# controller.net
KiCad netlist of a schematic drawn in Altium Designer
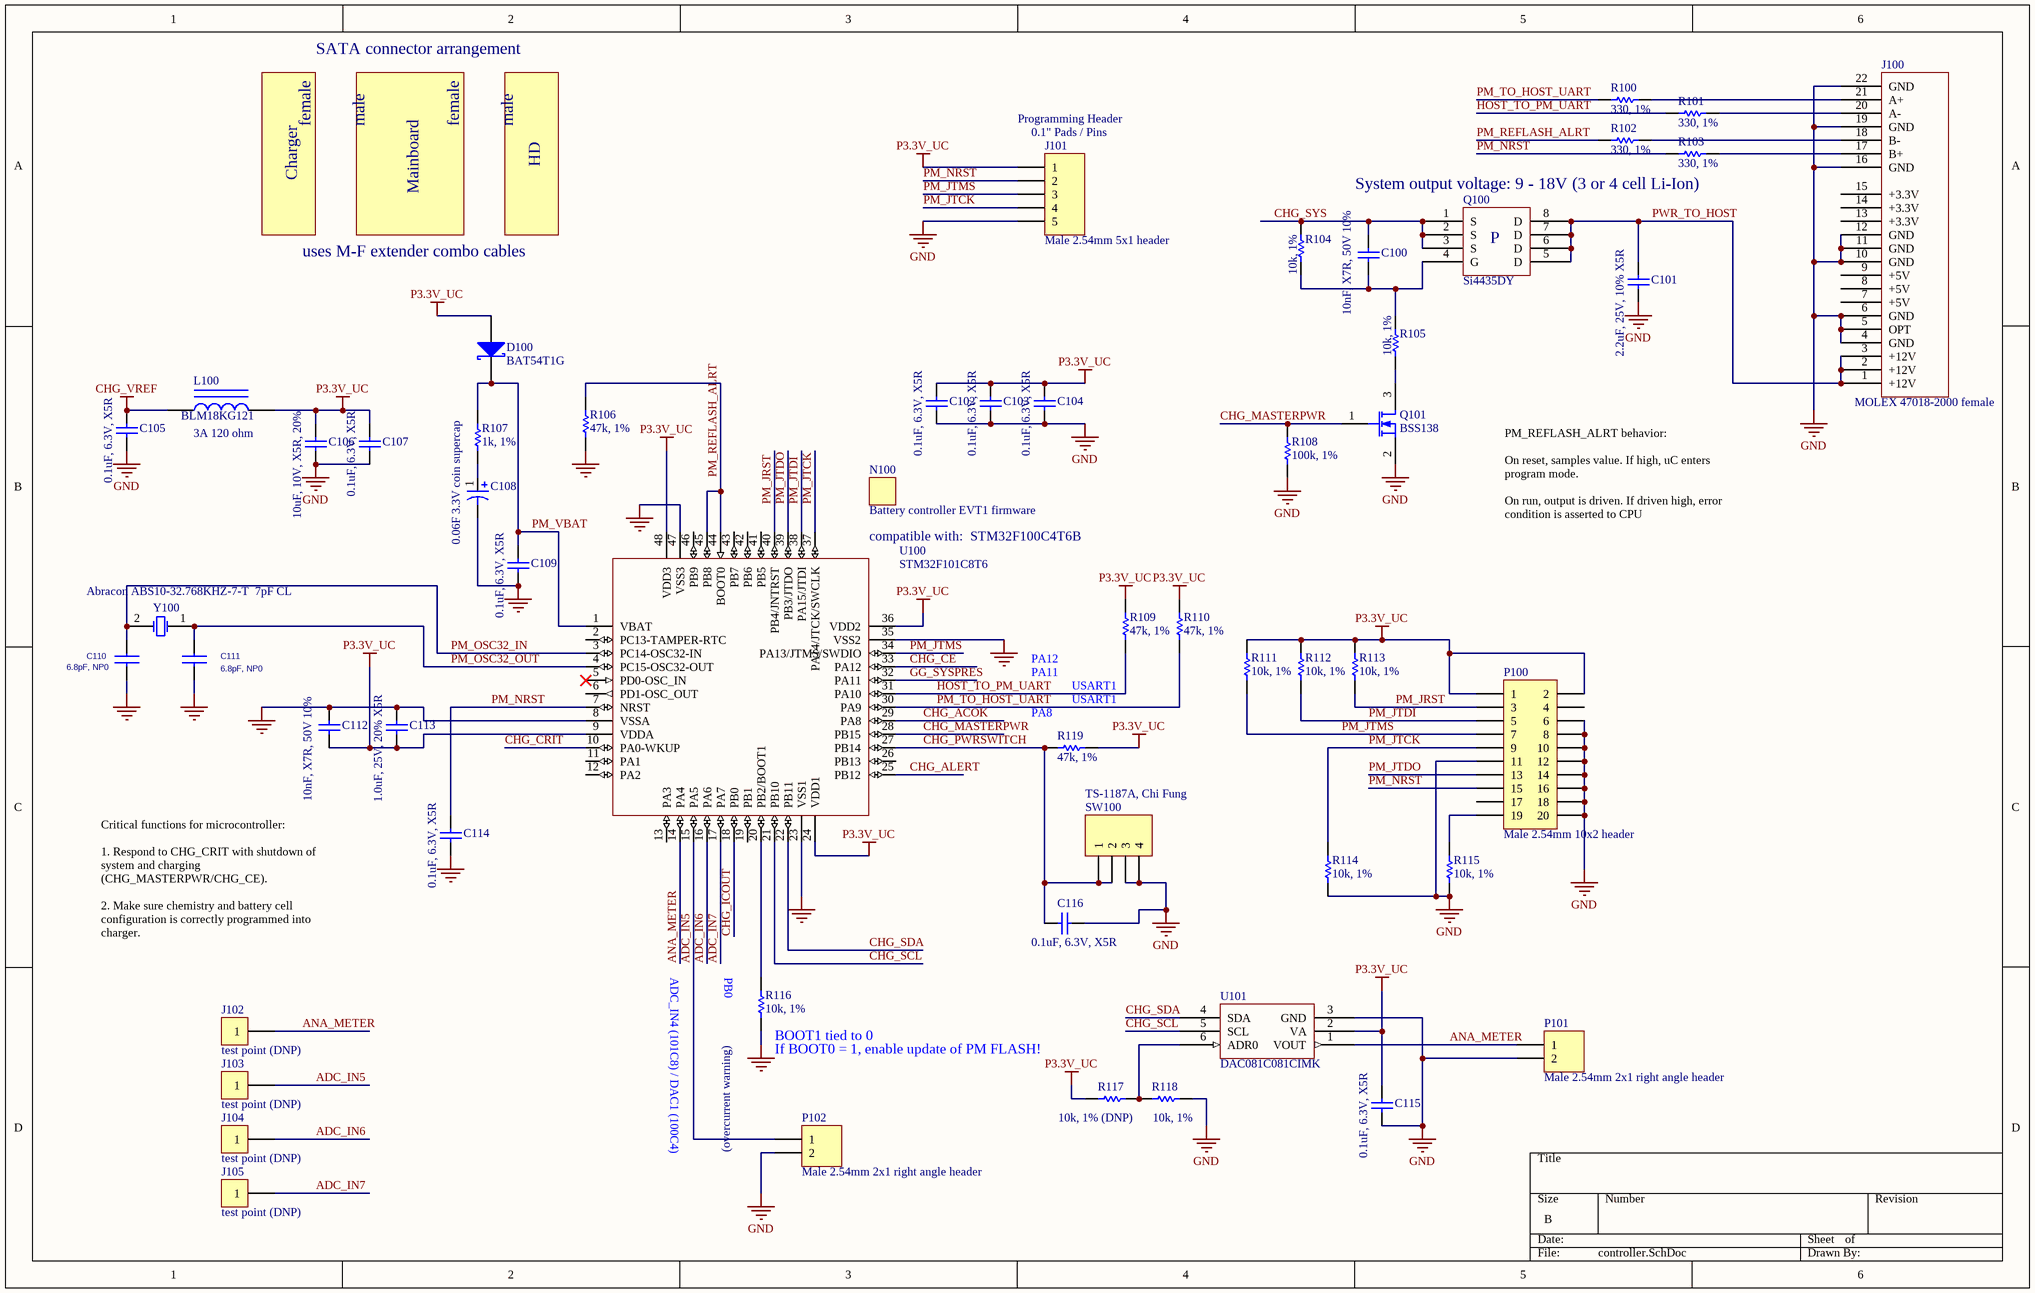
[diagram p0: controller.SchDoc]

(export (version "E")
  (design (tool "Eeschema 10.0.6"))
  (components
    (comp (ref "C100")
      (value "10nF, X7R, 50V 10%")
      (footprint "CAPC1005N")
      (description "Capacitor (Semiconductor SIM Model)")
      (fields (field (name "PUBLISHER") "Altium Limited"))
      (libsource (lib "Miscellaneous Devices") (part "Cap Semi"))
    )
    (comp (ref "C101")
      (value "2.2uF, 25V, 10% X5R")
      (footprint "CAPC1608N")
      (description "Capacitor (Semiconductor SIM Model)")
      (fields (field (name "PUBLISHER") "Altium Limited"))
      (libsource (lib "Miscellaneous Devices") (part "Cap Semi"))
    )
    (comp (ref "C102")
      (value "0.1uF, 6.3V, X5R")
      (footprint "CAPC0603N_B")
      (description "Capacitor (Semiconductor SIM Model)")
      (fields (field (name "PUBLISHER") "Altium Limited"))
      (libsource (lib "Miscellaneous Devices") (part "Cap Semi"))
    )
    (comp (ref "C103")
      (value "0.1uF, 6.3V, X5R")
      (footprint "CAPC0603N_B")
      (description "Capacitor (Semiconductor SIM Model)")
      (fields (field (name "PUBLISHER") "Altium Limited"))
      (libsource (lib "Miscellaneous Devices") (part "Cap Semi"))
    )
    (comp (ref "C104")
      (value "0.1uF, 6.3V, X5R")
      (footprint "CAPC0603N_B")
      (description "Capacitor (Semiconductor SIM Model)")
      (fields (field (name "PUBLISHER") "Altium Limited"))
      (libsource (lib "Miscellaneous Devices") (part "Cap Semi"))
    )
    (comp (ref "C105")
      (value "0.1uF, 6.3V, X5R")
      (footprint "CAPC0603N_B")
      (description "Capacitor (Semiconductor SIM Model)")
      (fields (field (name "PUBLISHER") "Altium Limited"))
      (libsource (lib "Miscellaneous Devices") (part "Cap Semi"))
    )
    (comp (ref "C106")
      (value "10uF, 10V, X5R, 20%")
      (footprint "CAPC1608N")
      (description "Capacitor (Semiconductor SIM Model)")
      (fields (field (name "PUBLISHER") "Altium Limited"))
      (libsource (lib "Miscellaneous Devices") (part "Cap Semi"))
    )
    (comp (ref "C107")
      (value "0.1uF, 6.3V, X5R")
      (footprint "CAPC0603N_B")
      (description "Capacitor (Semiconductor SIM Model)")
      (fields (field (name "PUBLISHER") "Altium Limited"))
      (libsource (lib "Miscellaneous Devices") (part "Cap Semi"))
    )
    (comp (ref "C108")
      (value "0.06F 3.3V coin supercap")
      (footprint "TAIYO_YUDEN_PAS414HR-VA5R")
      (description "Taiyo Yuden PAS414HR-VA5R")
      (fields (field (name "PUBLISHER") "Altium Limited"))
      (libsource (lib "Miscellaneous Devices") (part "Cap Pol3"))
    )
    (comp (ref "C109")
      (value "0.1uF, 6.3V, X5R")
      (footprint "CAPC0603N_B")
      (description "Capacitor (Semiconductor SIM Model)")
      (fields (field (name "PUBLISHER") "Altium Limited"))
      (libsource (lib "Miscellaneous Devices") (part "Cap Semi"))
    )
    (comp (ref "C110") (value "6.8pF, NP0") (libsource (lib "*") (part "CAP NP")))
    (comp (ref "C111") (value "6.8pF, NP0") (libsource (lib "*") (part "CAP NP")))
    (comp (ref "C112")
      (value "10nF, X7R, 50V 10%")
      (footprint "CAPC1005N")
      (description "Capacitor (Semiconductor SIM Model)")
      (fields (field (name "PUBLISHER") "Altium Limited"))
      (libsource (lib "Miscellaneous Devices") (part "Cap Semi"))
    )
    (comp (ref "C113")
      (value "1.0uF, 25V, 20% X5R")
      (footprint "CAPC1608N")
      (description "Capacitor (Semiconductor SIM Model)")
      (fields (field (name "PUBLISHER") "Altium Limited"))
      (libsource (lib "Miscellaneous Devices") (part "Cap Semi"))
    )
    (comp (ref "C114")
      (value "0.1uF, 6.3V, X5R")
      (footprint "CAPC0603N_B")
      (description "Capacitor (Semiconductor SIM Model)")
      (fields (field (name "PUBLISHER") "Altium Limited"))
      (libsource (lib "Miscellaneous Devices") (part "Cap Semi"))
    )
    (comp (ref "C115")
      (value "0.1uF, 6.3V, X5R")
      (footprint "CAPC0603N_B")
      (description "Capacitor (Semiconductor SIM Model)")
      (fields (field (name "PUBLISHER") "Altium Limited"))
      (libsource (lib "Miscellaneous Devices") (part "Cap Semi"))
    )
    (comp (ref "C116")
      (value "0.1uF, 6.3V, X5R")
      (footprint "CAPC0603N_B")
      (description "Capacitor (Semiconductor SIM Model)")
      (fields (field (name "PUBLISHER") "Altium Limited"))
      (libsource (lib "Miscellaneous Devices") (part "Cap Semi"))
    )
    (comp (ref "D100")
      (value "BAT54T1G")
      (footprint "SOD123")
      (description "Schottky Diode")
      (fields (field (name "PUBLISHER") "Altium Limited"))
      (libsource (lib "Miscellaneous Devices") (part "D Schottky"))
    )
    (comp (ref "J100")
      (value "MOLEX 47018-2000 female")
      (footprint "SATA_MOLEX_47018_2000")
      (description "SATA+Power connector")
      (libsource (lib "commonsch") (part "SATA_22P_HEADER"))
    )
    (comp (ref "J101")
      (value "Male 2.54mm 5x1 header")
      (footprint "HDR1X5")
      (description "Header, 5-Pin")
      (fields (field (name "PUBLISHER") "Altium Limited"))
      (libsource (lib "Miscellaneous Connectors") (part "Header 5"))
    )
    (comp (ref "J102")
      (value "test point (DNP)")
      (footprint "TP_SMT_38mil")
      (description "Connector")
      (libsource (lib "*") (part "CON1"))
    )
    (comp (ref "J103")
      (value "test point (DNP)")
      (footprint "TP_SMT_38mil")
      (description "Connector")
      (libsource (lib "*") (part "CON1"))
    )
    (comp (ref "J104")
      (value "test point (DNP)")
      (footprint "TP_SMT_38mil")
      (description "Connector")
      (libsource (lib "*") (part "CON1"))
    )
    (comp (ref "J105")
      (value "test point (DNP)")
      (footprint "TP_SMT_38mil")
      (description "Connector")
      (libsource (lib "*") (part "CON1"))
    )
    (comp (ref "L100")
      (value "BLM18KG121")
      (footprint "INDC1608AN")
      (description "Magnetic-Core Inductor")
      (fields (field (name "ALTIUM_VALUE") "3A 120 ohm") (field (name "PUBLISHER") "Altium Limited"))
      (libsource (lib "Miscellaneous Devices") (part "Inductor Iron"))
    )
    (comp (ref "N100")
      (value "Battery controller EVT1 firmware")
      (description "Placeholder for non-electrical BOM items")
      (libsource (lib "commonsch") (part "NOTE"))
    )
    (comp (ref "P100")
      (value "Male 2.54mm 10x2 header")
      (footprint "HDR2X10")
      (description "Header, 10-Pin, Dual row")
      (fields (field (name "PUBLISHER") "Altium Limited"))
      (libsource (lib "Miscellaneous Connectors") (part "Header 10X2"))
    )
    (comp (ref "P101")
      (value "Male 2.54mm 2x1 right angle header")
      (footprint "HDR1X2H")
      (description "Header, 2-Pin, Right Angle")
      (fields (field (name "PUBLISHER") "Altium Limited"))
      (libsource (lib "Miscellaneous Connectors") (part "Header 2H"))
    )
    (comp (ref "P102")
      (value "Male 2.54mm 2x1 right angle header")
      (footprint "HDR1X2H")
      (description "Header, 2-Pin, Right Angle")
      (fields (field (name "PUBLISHER") "Altium Limited"))
      (libsource (lib "Miscellaneous Connectors") (part "Header 2H"))
    )
    (comp (ref "Q100")
      (value "Si4435DY")
      (footprint "SOIC127P600-8AN")
      (description "Singre P-channel FET, 8A, 30V")
      (libsource (lib "commonsch") (part "Si4435DY"))
    )
    (comp (ref "Q101")
      (value "BSS138")
      (footprint "SOT23-3N")
      (description "N-Channel MOSFET")
      (fields (field (name "PUBLISHER") "Altium Limited"))
      (libsource (lib "Miscellaneous Devices") (part "MOSFET-N"))
    )
    (comp (ref "R100")
      (value "330, 1%")
      (footprint "RESC1005N")
      (description "Resistor")
      (fields (field (name "PUBLISHER") "Altium Limited"))
      (libsource (lib "Miscellaneous Devices") (part "Res1"))
    )
    (comp (ref "R101")
      (value "330, 1%")
      (footprint "RESC1005N")
      (description "Resistor")
      (fields (field (name "PUBLISHER") "Altium Limited"))
      (libsource (lib "Miscellaneous Devices") (part "Res1"))
    )
    (comp (ref "R102")
      (value "330, 1%")
      (footprint "RESC1005N")
      (description "Resistor")
      (fields (field (name "PUBLISHER") "Altium Limited"))
      (libsource (lib "Miscellaneous Devices") (part "Res1"))
    )
    (comp (ref "R103")
      (value "330, 1%")
      (footprint "RESC1005N")
      (description "Resistor")
      (fields (field (name "PUBLISHER") "Altium Limited"))
      (libsource (lib "Miscellaneous Devices") (part "Res1"))
    )
    (comp (ref "R104")
      (value "10k, 1%")
      (footprint "RESC1005N")
      (description "Resistor")
      (fields (field (name "PUBLISHER") "Altium Limited"))
      (libsource (lib "Miscellaneous Devices") (part "Res1"))
    )
    (comp (ref "R105")
      (value "10k, 1%")
      (footprint "RESC1005N")
      (description "Resistor")
      (fields (field (name "PUBLISHER") "Altium Limited"))
      (libsource (lib "Miscellaneous Devices") (part "Res1"))
    )
    (comp (ref "R106")
      (value "47k, 1%")
      (footprint "RESC1005N")
      (description "Resistor")
      (fields (field (name "PUBLISHER") "Altium Limited"))
      (libsource (lib "Miscellaneous Devices") (part "Res1"))
    )
    (comp (ref "R107")
      (value "1k, 1%")
      (footprint "RESC1005N")
      (description "Resistor")
      (fields (field (name "PUBLISHER") "Altium Limited"))
      (libsource (lib "Miscellaneous Devices") (part "Res1"))
    )
    (comp (ref "R108")
      (value "100k, 1%")
      (footprint "RESC1005N")
      (description "Resistor")
      (fields (field (name "PUBLISHER") "Altium Limited"))
      (libsource (lib "Miscellaneous Devices") (part "Res1"))
    )
    (comp (ref "R109")
      (value "47k, 1%")
      (footprint "RESC1005N")
      (description "Resistor")
      (fields (field (name "PUBLISHER") "Altium Limited"))
      (libsource (lib "Miscellaneous Devices") (part "Res1"))
    )
    (comp (ref "R110")
      (value "47k, 1%")
      (footprint "RESC1005N")
      (description "Resistor")
      (fields (field (name "PUBLISHER") "Altium Limited"))
      (libsource (lib "Miscellaneous Devices") (part "Res1"))
    )
    (comp (ref "R111")
      (value "10k, 1%")
      (footprint "RESC1005N")
      (description "Resistor")
      (fields (field (name "PUBLISHER") "Altium Limited"))
      (libsource (lib "Miscellaneous Devices") (part "Res1"))
    )
    (comp (ref "R112")
      (value "10k, 1%")
      (footprint "RESC1005N")
      (description "Resistor")
      (fields (field (name "PUBLISHER") "Altium Limited"))
      (libsource (lib "Miscellaneous Devices") (part "Res1"))
    )
    (comp (ref "R113")
      (value "10k, 1%")
      (footprint "RESC1005N")
      (description "Resistor")
      (fields (field (name "PUBLISHER") "Altium Limited"))
      (libsource (lib "Miscellaneous Devices") (part "Res1"))
    )
    (comp (ref "R114")
      (value "10k, 1%")
      (footprint "RESC1005N")
      (description "Resistor")
      (fields (field (name "PUBLISHER") "Altium Limited"))
      (libsource (lib "Miscellaneous Devices") (part "Res1"))
    )
    (comp (ref "R115")
      (value "10k, 1%")
      (footprint "RESC1005N")
      (description "Resistor")
      (fields (field (name "PUBLISHER") "Altium Limited"))
      (libsource (lib "Miscellaneous Devices") (part "Res1"))
    )
    (comp (ref "R116")
      (value "10k, 1%")
      (footprint "RESC1005N")
      (description "Resistor")
      (fields (field (name "PUBLISHER") "Altium Limited"))
      (libsource (lib "Miscellaneous Devices") (part "Res1"))
    )
    (comp (ref "R117")
      (value "10k, 1% (DNP)")
      (footprint "RESC1005N")
      (description "Resistor")
      (fields (field (name "PUBLISHER") "Altium Limited"))
      (libsource (lib "Miscellaneous Devices") (part "Res1"))
    )
    (comp (ref "R118")
      (value "10k, 1%")
      (footprint "RESC1005N")
      (description "Resistor")
      (fields (field (name "PUBLISHER") "Altium Limited"))
      (libsource (lib "Miscellaneous Devices") (part "Res1"))
    )
    (comp (ref "R119")
      (value "47k, 1%")
      (footprint "RESC1005N")
      (description "Resistor")
      (fields (field (name "PUBLISHER") "Altium Limited"))
      (libsource (lib "Miscellaneous Devices") (part "Res1"))
    )
    (comp (ref "SW100")
      (value "TS-1187A, Chi Fung")
      (footprint "SWITCH_TS-1187A")
      (description "Chi Fung TS-1187A")
      (fields (field (name "PUBLISHER") "Altium Limited"))
      (libsource (lib "Miscellaneous Connectors") (part "Header 4"))
    )
    (comp (ref "U100")
      (value "STM32F101C8T6")
      (footprint "TSQFP50P900X900-48N")
      (description "32-bit ARM Coretex high performance microcontroller")
      (libsource (lib "*") (part "STM32F103C8T6"))
    )
    (comp (ref "U101")
      (value "DAC081C081CIMK")
      (footprint "SOT26A-6N")
      (description "Single 8-bit DAC for I2C bus")
      (libsource (lib "commonsch") (part "DAC081C81CIMK"))
    )
    (comp (ref "Y100")
      (value "Abracon ABS10-32.768KHZ-7-T  7pF CL")
      (footprint "ABS10-32.768KHZ")
      (description "Crystal Oscillator")
      (fields (field (name "PUBLISHER") "Altium Limited"))
      (libsource (lib "Miscellaneous Devices") (part "XTAL"))
    )
  )
  (nets
    (net (code "1") (name "/ADC_IN5") (class "Default")
      (node (ref "J103") (pin "1") (pinfunction "1_1") (pintype "passive"))
      (node (ref "P102") (pin "1") (pinfunction "1_1") (pintype "passive"))
      (node (ref "U100") (pin "15") (pinfunction "PA5_15") (pintype "bidirectional"))
    )
    (net (code "2") (name "/ADC_IN6") (class "Default")
      (node (ref "J104") (pin "1") (pinfunction "1_1") (pintype "passive"))
      (node (ref "U100") (pin "16") (pinfunction "PA6_16") (pintype "bidirectional"))
    )
    (net (code "3") (name "/ADC_IN7") (class "Default")
      (node (ref "J105") (pin "1") (pinfunction "1_1") (pintype "passive"))
      (node (ref "U100") (pin "17") (pinfunction "PA7_17") (pintype "bidirectional"))
    )
    (net (code "4") (name "/ANA_METER") (class "Default")
      (node (ref "J102") (pin "1") (pinfunction "1_1") (pintype "passive"))
      (node (ref "P101") (pin "1") (pinfunction "1_1") (pintype "passive"))
      (node (ref "U100") (pin "14") (pinfunction "PA4_14") (pintype "bidirectional"))
      (node (ref "U101") (pin "1") (pinfunction "VOUT_1") (pintype "output"))
    )
    (net (code "5") (name "/CHG_ACOK") (class "Default")
      (node (ref "U100") (pin "29") (pinfunction "PA8_29") (pintype "bidirectional"))
    )
    (net (code "6") (name "/CHG_ALERT") (class "Default")
      (node (ref "U100") (pin "25") (pinfunction "PB12_25") (pintype "bidirectional"))
    )
    (net (code "7") (name "/CHG_CE") (class "Default")
      (node (ref "U100") (pin "33") (pinfunction "PA12_33") (pintype "bidirectional"))
    )
    (net (code "8") (name "/CHG_CRIT") (class "Default")
      (node (ref "U100") (pin "10") (pinfunction "PA0-WKUP_10") (pintype "bidirectional"))
    )
    (net (code "9") (name "/CHG_ICOUT") (class "Default")
      (node (ref "U100") (pin "18") (pinfunction "PB0_18") (pintype "bidirectional"))
    )
    (net (code "10") (name "/CHG_MASTERPWR") (class "Default")
      (node (ref "Q101") (pin "1") (pinfunction "G_1") (pintype "passive"))
      (node (ref "R108") (pin "2") (pinfunction "2_2") (pintype "passive"))
      (node (ref "U100") (pin "28") (pinfunction "PB15_28") (pintype "bidirectional"))
    )
    (net (code "11") (name "/CHG_PWRSWITCH") (class "Default")
      (node (ref "C116") (pin "2") (pinfunction "2_2") (pintype "passive"))
      (node (ref "R119") (pin "1") (pinfunction "1_1") (pintype "passive"))
      (node (ref "SW100") (pin "1") (pinfunction "1_1") (pintype "passive"))
      (node (ref "SW100") (pin "2") (pinfunction "2_2") (pintype "passive"))
      (node (ref "U100") (pin "27") (pinfunction "PB14_27") (pintype "bidirectional"))
    )
    (net (code "12") (name "/CHG_SCL") (class "Default")
      (node (ref "U100") (pin "21") (pinfunction "PB10_21") (pintype "bidirectional"))
      (node (ref "U101") (pin "5") (pinfunction "SCL_5") (pintype "open_collector"))
    )
    (net (code "13") (name "/CHG_SDA") (class "Default")
      (node (ref "U100") (pin "22") (pinfunction "PB11_22") (pintype "bidirectional"))
      (node (ref "U101") (pin "4") (pinfunction "SDA_4") (pintype "open_collector"))
    )
    (net (code "14") (name "/CHG_SYS") (class "Default")
      (node (ref "C100") (pin "1") (pinfunction "1_1") (pintype "passive"))
      (node (ref "Q100") (pin "1") (pinfunction "S_1") (pintype "passive"))
      (node (ref "Q100") (pin "2") (pinfunction "S_2") (pintype "passive"))
      (node (ref "Q100") (pin "3") (pinfunction "S_3") (pintype "passive"))
      (node (ref "R104") (pin "2") (pinfunction "2_2") (pintype "passive"))
    )
    (net (code "15") (name "/GG_SYSPRES") (class "Default")
      (node (ref "U100") (pin "32") (pinfunction "PA11_32") (pintype "bidirectional"))
    )
    (net (code "16") (name "/HOST_TO_PM_UART") (class "Default")
      (node (ref "R101") (pin "1") (pinfunction "1_1") (pintype "passive"))
      (node (ref "R109") (pin "1") (pinfunction "1_1") (pintype "passive"))
      (node (ref "U100") (pin "31") (pinfunction "PA10_31") (pintype "bidirectional"))
    )
    (net (code "17") (name "/PM_JRST") (class "Default")
      (node (ref "P100") (pin "3") (pinfunction "3_3") (pintype "passive"))
      (node (ref "R113") (pin "1") (pinfunction "1_1") (pintype "passive"))
      (node (ref "U100") (pin "40") (pinfunction "PB4/JNTRST_40") (pintype "bidirectional"))
    )
    (net (code "18") (name "/PM_JTCK") (class "Default")
      (node (ref "J101") (pin "4") (pinfunction "4_4") (pintype "passive"))
      (node (ref "P100") (pin "9") (pinfunction "9_9") (pintype "passive"))
      (node (ref "R114") (pin "2") (pinfunction "2_2") (pintype "passive"))
      (node (ref "U100") (pin "37") (pinfunction "PA14/JTCK/SWCLK_37") (pintype "bidirectional"))
    )
    (net (code "19") (name "/PM_JTDI") (class "Default")
      (node (ref "P100") (pin "5") (pinfunction "5_5") (pintype "passive"))
      (node (ref "R112") (pin "1") (pinfunction "1_1") (pintype "passive"))
      (node (ref "U100") (pin "38") (pinfunction "PA15/JTDI_38") (pintype "bidirectional"))
    )
    (net (code "20") (name "/PM_JTDO") (class "Default")
      (node (ref "P100") (pin "13") (pinfunction "13_13") (pintype "passive"))
      (node (ref "U100") (pin "39") (pinfunction "PB3/JTDO_39") (pintype "bidirectional"))
    )
    (net (code "21") (name "/PM_JTMS") (class "Default")
      (node (ref "J101") (pin "3") (pinfunction "3_3") (pintype "passive"))
      (node (ref "P100") (pin "7") (pinfunction "7_7") (pintype "passive"))
      (node (ref "R111") (pin "1") (pinfunction "1_1") (pintype "passive"))
      (node (ref "U100") (pin "34") (pinfunction "PA13/JTMS/SWDIO_34") (pintype "bidirectional"))
    )
    (net (code "22") (name "/PM_NRST") (class "Default")
      (node (ref "C114") (pin "1") (pinfunction "1_1") (pintype "passive"))
      (node (ref "J101") (pin "2") (pinfunction "2_2") (pintype "passive"))
      (node (ref "P100") (pin "15") (pinfunction "15_15") (pintype "passive"))
      (node (ref "R103") (pin "1") (pinfunction "1_1") (pintype "passive"))
      (node (ref "U100") (pin "7") (pinfunction "NRST_7") (pintype "bidirectional"))
    )
    (net (code "23") (name "/PM_OSC32_IN") (class "Default")
      (node (ref "C110") (pin "1") (pinfunction "1_1") (pintype "passive"))
      (node (ref "U100") (pin "3") (pinfunction "PC14-OSC32-IN_3") (pintype "bidirectional"))
      (node (ref "Y100") (pin "2") (pinfunction "OSC2_2") (pintype "passive"))
    )
    (net (code "24") (name "/PM_OSC32_OUT") (class "Default")
      (node (ref "C111") (pin "1") (pinfunction "1_1") (pintype "passive"))
      (node (ref "U100") (pin "4") (pinfunction "PC15-OSC32-OUT_4") (pintype "bidirectional"))
      (node (ref "Y100") (pin "1") (pinfunction "OSC1_1") (pintype "passive"))
    )
    (net (code "25") (name "/PM_REFLASH_ALRT") (class "Default")
      (node (ref "R102") (pin "1") (pinfunction "1_1") (pintype "passive"))
      (node (ref "R106") (pin "2") (pinfunction "2_2") (pintype "passive"))
      (node (ref "U100") (pin "44") (pinfunction "BOOT0_44") (pintype "input"))
      (node (ref "U100") (pin "45") (pinfunction "PB8_45") (pintype "bidirectional"))
    )
    (net (code "26") (name "/PM_TO_HOST_UART") (class "Default")
      (node (ref "R100") (pin "1") (pinfunction "1_1") (pintype "passive"))
      (node (ref "R110") (pin "1") (pinfunction "1_1") (pintype "passive"))
      (node (ref "U100") (pin "30") (pinfunction "PA9_30") (pintype "bidirectional"))
    )
    (net (code "27") (name "/PM_VBAT") (class "Default")
      (node (ref "C109") (pin "1") (pinfunction "1_1") (pintype "passive"))
      (node (ref "D100") (pin "2") (pinfunction "K_2") (pintype "passive"))
      (node (ref "R107") (pin "2") (pinfunction "2_2") (pintype "passive"))
      (node (ref "U100") (pin "1") (pinfunction "VBAT_1") (pintype "power_in"))
    )
    (net (code "28") (name "/PWR_TO_HOST") (class "Default")
      (node (ref "C101") (pin "1") (pinfunction "1_1") (pintype "passive"))
      (node (ref "J100") (pin "1") (pinfunction "+12V_1") (pintype "power_in"))
      (node (ref "J100") (pin "2") (pinfunction "+12V_2") (pintype "power_in"))
      (node (ref "J100") (pin "3") (pinfunction "+12V_3") (pintype "power_in"))
      (node (ref "Q100") (pin "5") (pinfunction "D_5") (pintype "passive"))
      (node (ref "Q100") (pin "6") (pinfunction "D_6") (pintype "passive"))
      (node (ref "Q100") (pin "7") (pinfunction "D_7") (pintype "passive"))
      (node (ref "Q100") (pin "8") (pinfunction "D_8") (pintype "passive"))
    )
    (net (code "29") (name "CHG_VREF") (class "Default")
      (node (ref "C105") (pin "1") (pinfunction "1_1") (pintype "passive"))
      (node (ref "L100") (pin "1") (pinfunction "1_1") (pintype "passive"))
    )
    (net (code "30") (name "GND") (class "Default")
      (node (ref "C101") (pin "2") (pinfunction "2_2") (pintype "passive"))
      (node (ref "C102") (pin "2") (pinfunction "2_2") (pintype "passive"))
      (node (ref "C103") (pin "2") (pinfunction "2_2") (pintype "passive"))
      (node (ref "C104") (pin "2") (pinfunction "2_2") (pintype "passive"))
      (node (ref "C105") (pin "2") (pinfunction "2_2") (pintype "passive"))
      (node (ref "C106") (pin "2") (pinfunction "2_2") (pintype "passive"))
      (node (ref "C107") (pin "2") (pinfunction "2_2") (pintype "passive"))
      (node (ref "C108") (pin "2") (pinfunction "2_2") (pintype "passive"))
      (node (ref "C109") (pin "2") (pinfunction "2_2") (pintype "passive"))
      (node (ref "C110") (pin "2") (pinfunction "2_2") (pintype "passive"))
      (node (ref "C111") (pin "2") (pinfunction "2_2") (pintype "passive"))
      (node (ref "C112") (pin "1") (pinfunction "1_1") (pintype "passive"))
      (node (ref "C113") (pin "1") (pinfunction "1_1") (pintype "passive"))
      (node (ref "C114") (pin "2") (pinfunction "2_2") (pintype "passive"))
      (node (ref "C115") (pin "2") (pinfunction "2_2") (pintype "passive"))
      (node (ref "C116") (pin "1") (pinfunction "1_1") (pintype "passive"))
      (node (ref "J100") (pin "10") (pinfunction "GND_10") (pintype "power_in"))
      (node (ref "J100") (pin "11") (pinfunction "GND_11") (pintype "power_in"))
      (node (ref "J100") (pin "12") (pinfunction "GND_12") (pintype "power_in"))
      (node (ref "J100") (pin "16") (pinfunction "GND_16") (pintype "power_in"))
      (node (ref "J100") (pin "19") (pinfunction "GND_19") (pintype "power_in"))
      (node (ref "J100") (pin "22") (pinfunction "GND_22") (pintype "power_in"))
      (node (ref "J100") (pin "4") (pinfunction "GND_4") (pintype "power_in"))
      (node (ref "J100") (pin "5") (pinfunction "OPT_5") (pintype "passive"))
      (node (ref "J100") (pin "6") (pinfunction "GND_6") (pintype "power_in"))
      (node (ref "J101") (pin "5") (pinfunction "5_5") (pintype "passive"))
      (node (ref "P100") (pin "10") (pinfunction "10_10") (pintype "passive"))
      (node (ref "P100") (pin "11") (pinfunction "11_11") (pintype "passive"))
      (node (ref "P100") (pin "12") (pinfunction "12_12") (pintype "passive"))
      (node (ref "P100") (pin "14") (pinfunction "14_14") (pintype "passive"))
      (node (ref "P100") (pin "16") (pinfunction "16_16") (pintype "passive"))
      (node (ref "P100") (pin "18") (pinfunction "18_18") (pintype "passive"))
      (node (ref "P100") (pin "20") (pinfunction "20_20") (pintype "passive"))
      (node (ref "P100") (pin "6") (pinfunction "6_6") (pintype "passive"))
      (node (ref "P100") (pin "8") (pinfunction "8_8") (pintype "passive"))
      (node (ref "P101") (pin "2") (pinfunction "2_2") (pintype "passive"))
      (node (ref "P102") (pin "2") (pinfunction "2_2") (pintype "passive"))
      (node (ref "Q101") (pin "2") (pinfunction "S_2") (pintype "passive"))
      (node (ref "R106") (pin "1") (pinfunction "1_1") (pintype "passive"))
      (node (ref "R108") (pin "1") (pinfunction "1_1") (pintype "passive"))
      (node (ref "R114") (pin "1") (pinfunction "1_1") (pintype "passive"))
      (node (ref "R115") (pin "1") (pinfunction "1_1") (pintype "passive"))
      (node (ref "R116") (pin "1") (pinfunction "1_1") (pintype "passive"))
      (node (ref "R118") (pin "2") (pinfunction "2_2") (pintype "passive"))
      (node (ref "SW100") (pin "3") (pinfunction "3_3") (pintype "passive"))
      (node (ref "SW100") (pin "4") (pinfunction "4_4") (pintype "passive"))
      (node (ref "U100") (pin "23") (pinfunction "VSS1_23") (pintype "power_in"))
      (node (ref "U100") (pin "35") (pinfunction "VSS2_35") (pintype "power_in"))
      (node (ref "U100") (pin "47") (pinfunction "VSS3_47") (pintype "power_in"))
      (node (ref "U100") (pin "8") (pinfunction "VSSA_8") (pintype "power_in"))
      (node (ref "U101") (pin "3") (pinfunction "GND_3") (pintype "power_in"))
    )
    (net (code "31") (name "Net-(C108-Pad1)") (class "Default")
      (node (ref "C108") (pin "1") (pinfunction "1_1") (pintype "passive"))
      (node (ref "R107") (pin "1") (pinfunction "1_1") (pintype "passive"))
    )
    (net (code "32") (name "Net-(J100-A+)") (class "Default")
      (node (ref "J100") (pin "21") (pinfunction "A+_21") (pintype "passive"))
      (node (ref "R100") (pin "2") (pinfunction "2_2") (pintype "passive"))
    )
    (net (code "33") (name "Net-(J100-A-)") (class "Default")
      (node (ref "J100") (pin "20") (pinfunction "A-_20") (pintype "passive"))
      (node (ref "R101") (pin "2") (pinfunction "2_2") (pintype "passive"))
    )
    (net (code "34") (name "Net-(J100-B+)") (class "Default")
      (node (ref "J100") (pin "17") (pinfunction "B+_17") (pintype "passive"))
      (node (ref "R103") (pin "2") (pinfunction "2_2") (pintype "passive"))
    )
    (net (code "35") (name "Net-(J100-B-)") (class "Default")
      (node (ref "J100") (pin "18") (pinfunction "B-_18") (pintype "passive"))
      (node (ref "R102") (pin "2") (pinfunction "2_2") (pintype "passive"))
    )
    (net (code "36") (name "Net-(P100-Pad19)") (class "Default")
      (node (ref "P100") (pin "19") (pinfunction "19_19") (pintype "passive"))
      (node (ref "R115") (pin "2") (pinfunction "2_2") (pintype "passive"))
    )
    (net (code "37") (name "Net-(Q100-G)") (class "Default")
      (node (ref "C100") (pin "2") (pinfunction "2_2") (pintype "passive"))
      (node (ref "Q100") (pin "4") (pinfunction "G_4") (pintype "passive"))
      (node (ref "R104") (pin "1") (pinfunction "1_1") (pintype "passive"))
      (node (ref "R105") (pin "2") (pinfunction "2_2") (pintype "passive"))
    )
    (net (code "38") (name "Net-(Q101-D)") (class "Default")
      (node (ref "Q101") (pin "3") (pinfunction "D_3") (pintype "passive"))
      (node (ref "R105") (pin "1") (pinfunction "1_1") (pintype "passive"))
    )
    (net (code "39") (name "Net-(U100-PB2{slash}BOOT1)") (class "Default")
      (node (ref "R116") (pin "2") (pinfunction "2_2") (pintype "passive"))
      (node (ref "U100") (pin "20") (pinfunction "PB2/BOOT1_20") (pintype "bidirectional"))
    )
    (net (code "40") (name "Net-(U101-ADR0)") (class "Default")
      (node (ref "R117") (pin "2") (pinfunction "2_2") (pintype "passive"))
      (node (ref "R118") (pin "1") (pinfunction "1_1") (pintype "passive"))
      (node (ref "U101") (pin "6") (pinfunction "ADR0_6") (pintype "input"))
    )
    (net (code "41") (name "P3.3V_UC") (class "Default")
      (node (ref "C102") (pin "1") (pinfunction "1_1") (pintype "passive"))
      (node (ref "C103") (pin "1") (pinfunction "1_1") (pintype "passive"))
      (node (ref "C104") (pin "1") (pinfunction "1_1") (pintype "passive"))
      (node (ref "C106") (pin "1") (pinfunction "1_1") (pintype "passive"))
      (node (ref "C107") (pin "1") (pinfunction "1_1") (pintype "passive"))
      (node (ref "C112") (pin "2") (pinfunction "2_2") (pintype "passive"))
      (node (ref "C113") (pin "2") (pinfunction "2_2") (pintype "passive"))
      (node (ref "C115") (pin "1") (pinfunction "1_1") (pintype "passive"))
      (node (ref "D100") (pin "1") (pinfunction "A_1") (pintype "passive"))
      (node (ref "J101") (pin "1") (pinfunction "1_1") (pintype "passive"))
      (node (ref "L100") (pin "2") (pinfunction "2_2") (pintype "passive"))
      (node (ref "P100") (pin "1") (pinfunction "1_1") (pintype "passive"))
      (node (ref "P100") (pin "2") (pinfunction "2_2") (pintype "passive"))
      (node (ref "R109") (pin "2") (pinfunction "2_2") (pintype "passive"))
      (node (ref "R110") (pin "2") (pinfunction "2_2") (pintype "passive"))
      (node (ref "R111") (pin "2") (pinfunction "2_2") (pintype "passive"))
      (node (ref "R112") (pin "2") (pinfunction "2_2") (pintype "passive"))
      (node (ref "R113") (pin "2") (pinfunction "2_2") (pintype "passive"))
      (node (ref "R117") (pin "1") (pinfunction "1_1") (pintype "passive"))
      (node (ref "R119") (pin "2") (pinfunction "2_2") (pintype "passive"))
      (node (ref "U100") (pin "24") (pinfunction "VDD1_24") (pintype "power_in"))
      (node (ref "U100") (pin "36") (pinfunction "VDD2_36") (pintype "power_in"))
      (node (ref "U100") (pin "48") (pinfunction "VDD3_48") (pintype "power_in"))
      (node (ref "U100") (pin "9") (pinfunction "VDDA_9") (pintype "power_in"))
      (node (ref "U101") (pin "2") (pinfunction "VA_2") (pintype "power_in"))
    )
    (net (code "42") (name "unconnected-(J100-+3.3V-Pad13)") (class "Default")
      (node (ref "J100") (pin "13") (pinfunction "+3.3V_13") (pintype "power_in"))
    )
    (net (code "43") (name "unconnected-(J100-+3.3V-Pad14)") (class "Default")
      (node (ref "J100") (pin "14") (pinfunction "+3.3V_14") (pintype "power_in"))
    )
    (net (code "44") (name "unconnected-(J100-+3.3V-Pad15)") (class "Default")
      (node (ref "J100") (pin "15") (pinfunction "+3.3V_15") (pintype "power_in"))
    )
    (net (code "45") (name "unconnected-(J100-+5V-Pad7)") (class "Default")
      (node (ref "J100") (pin "7") (pinfunction "+5V_7") (pintype "power_in"))
    )
    (net (code "46") (name "unconnected-(J100-+5V-Pad8)") (class "Default")
      (node (ref "J100") (pin "8") (pinfunction "+5V_8") (pintype "power_in"))
    )
    (net (code "47") (name "unconnected-(J100-+5V-Pad9)") (class "Default")
      (node (ref "J100") (pin "9") (pinfunction "+5V_9") (pintype "power_in"))
    )
    (net (code "48") (name "unconnected-(P100-Pad4)") (class "Default")
      (node (ref "P100") (pin "4") (pinfunction "4_4") (pintype "passive"))
    )
    (net (code "49") (name "unconnected-(P100-Pad17)") (class "Default")
      (node (ref "P100") (pin "17") (pinfunction "17_17") (pintype "passive"))
    )
    (net (code "50") (name "unconnected-(U100-PA1-Pad11)") (class "Default")
      (node (ref "U100") (pin "11") (pinfunction "PA1_11") (pintype "bidirectional"))
    )
    (net (code "51") (name "unconnected-(U100-PA2-Pad12)") (class "Default")
      (node (ref "U100") (pin "12") (pinfunction "PA2_12") (pintype "bidirectional"))
    )
    (net (code "52") (name "unconnected-(U100-PA3-Pad13)") (class "Default")
      (node (ref "U100") (pin "13") (pinfunction "PA3_13") (pintype "bidirectional"))
    )
    (net (code "53") (name "unconnected-(U100-PB1-Pad19)") (class "Default")
      (node (ref "U100") (pin "19") (pinfunction "PB1_19") (pintype "bidirectional"))
    )
    (net (code "54") (name "unconnected-(U100-PB5-Pad41)") (class "Default")
      (node (ref "U100") (pin "41") (pinfunction "PB5_41") (pintype "bidirectional"))
    )
    (net (code "55") (name "unconnected-(U100-PB6-Pad42)") (class "Default")
      (node (ref "U100") (pin "42") (pinfunction "PB6_42") (pintype "bidirectional"))
    )
    (net (code "56") (name "unconnected-(U100-PB7-Pad43)") (class "Default")
      (node (ref "U100") (pin "43") (pinfunction "PB7_43") (pintype "bidirectional"))
    )
    (net (code "57") (name "unconnected-(U100-PB9-Pad46)") (class "Default")
      (node (ref "U100") (pin "46") (pinfunction "PB9_46") (pintype "bidirectional"))
    )
    (net (code "58") (name "unconnected-(U100-PB13-Pad26)") (class "Default")
      (node (ref "U100") (pin "26") (pinfunction "PB13_26") (pintype "bidirectional"))
    )
    (net (code "59") (name "unconnected-(U100-PC13-TAMPER-RTC-Pad2)") (class "Default")
      (node (ref "U100") (pin "2") (pinfunction "PC13-TAMPER-RTC_2") (pintype "bidirectional"))
    )
    (net (code "60") (name "unconnected-(U100-PD0-OSC_IN-Pad5)") (class "Default")
      (node (ref "U100") (pin "5") (pinfunction "PD0-OSC_IN_5") (pintype "input+no_connect"))
    )
    (net (code "61") (name "unconnected-(U100-PD1-OSC_OUT-Pad6)") (class "Default")
      (node (ref "U100") (pin "6") (pinfunction "PD1-OSC_OUT_6") (pintype "output"))
    )
  )
)
